# power.net
KiCad netlist of a schematic drawn in Altium Designer
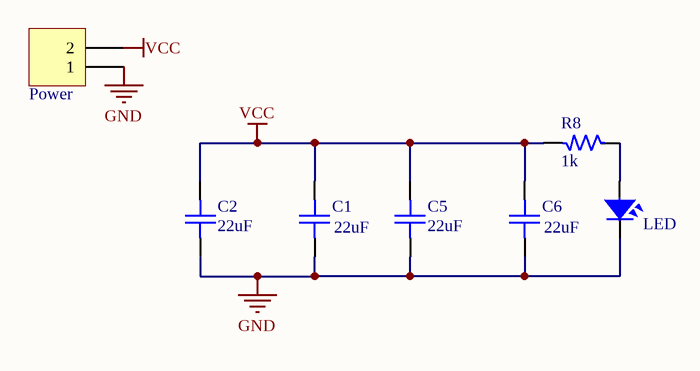
[diagram p0: power.SchDoc]

(export (version "E")
  (design (tool "Eeschema 10.0.6"))
  (components
    (comp (ref "C1")
      (value "22uF")
      (footprint "CAPC-0603 (1608)")
      (description "CAP CER 33pF 50V 5%  0603")
      (fields (field (name "MPN") "CL10C330JB8NNNC, 0603N330J500CT"))
      (libsource (lib "BYTECH_HW_LIB_2019 (1)") (part "0603N330J500CT"))
    )
    (comp (ref "C2")
      (value "22uF")
      (footprint "CAPC-0603 (1608)")
      (description "CAP CER 33pF 50V 5%  0603")
      (fields (field (name "MPN") "CL10C330JB8NNNC, 0603N330J500CT"))
      (libsource (lib "BYTECH_HW_LIB_2019 (1)") (part "0603N330J500CT"))
    )
    (comp (ref "C5")
      (value "22uF")
      (footprint "CAPC-0603 (1608)")
      (description "CAP CER 33pF 50V 5%  0603")
      (fields (field (name "MPN") "CL10C330JB8NNNC, 0603N330J500CT"))
      (libsource (lib "BYTECH_HW_LIB_2019 (1)") (part "0603N330J500CT"))
    )
    (comp (ref "C6")
      (value "22uF")
      (footprint "CAPC-0603 (1608)")
      (description "CAP CER 33pF 50V 5%  0603")
      (fields (field (name "MPN") "CL10C330JB8NNNC, 0603N330J500CT"))
      (libsource (lib "BYTECH_HW_LIB_2019 (1)") (part "0603N330J500CT"))
    )
    (comp (ref "LED")
      (value "LED")
      (footprint "LED-3")
      (description "LED Single colour Green and Red")
      (libsource (lib "echipkool-com-library") (part "LED"))
    )
    (comp (ref "Power")
      (value "Header 2_1")
      (footprint "HED2")
      (description "Header, 2-Pin")
      (fields (field (name "MANUFACTURER") "Generic Components"))
      (libsource (lib "echipkool-com-library") (part "Header 2_1"))
    )
    (comp (ref "R8")
      (value "1k")
      (footprint "SM-RES-1206")
      (description "Resistor 1/4W")
      (libsource (lib "echipkool-com-library") (part "R"))
    )
  )
  (nets
    (net (code "1") (name "GND") (class "Default")
      (node (ref "C1") (pin "1") (pinfunction "1_1") (pintype "passive"))
      (node (ref "C2") (pin "1") (pinfunction "1_1") (pintype "passive"))
      (node (ref "C5") (pin "1") (pinfunction "1_1") (pintype "passive"))
      (node (ref "C6") (pin "1") (pinfunction "1_1") (pintype "passive"))
      (node (ref "LED") (pin "2") (pinfunction "2_2") (pintype "passive"))
      (node (ref "Power") (pin "1") (pinfunction "1_1") (pintype "passive"))
    )
    (net (code "2") (name "Net-(LED-Pad1)") (class "Default")
      (node (ref "LED") (pin "1") (pinfunction "1_1") (pintype "passive"))
      (node (ref "R8") (pin "1") (pinfunction "1_1") (pintype "passive"))
    )
    (net (code "3") (name "VCC") (class "Default")
      (node (ref "C1") (pin "2") (pinfunction "2_2") (pintype "passive"))
      (node (ref "C2") (pin "2") (pinfunction "2_2") (pintype "passive"))
      (node (ref "C5") (pin "2") (pinfunction "2_2") (pintype "passive"))
      (node (ref "C6") (pin "2") (pinfunction "2_2") (pintype "passive"))
      (node (ref "Power") (pin "2") (pinfunction "2_2") (pintype "passive"))
      (node (ref "R8") (pin "2") (pinfunction "2_2") (pintype "passive"))
    )
  )
)
